# Power.net
KiCad netlist of a schematic drawn in Altium Designer
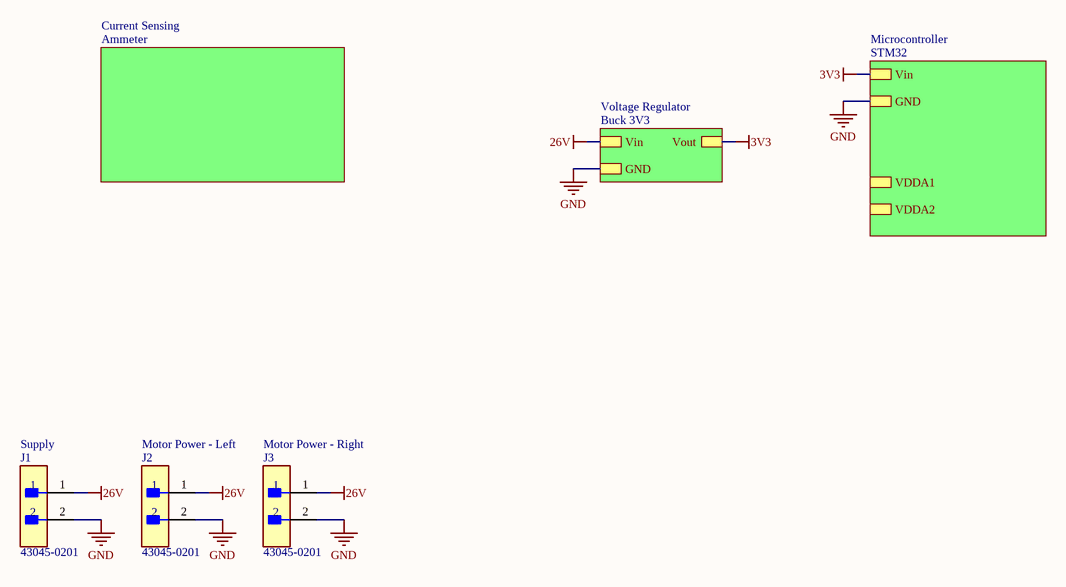
[diagram p0: Power.SchDoc]

(export (version "E")
  (design (tool "Eeschema 10.0.6"))
  (components
    (comp (ref "J1")
      (value "43045-0201")
      (footprint "FP-43045-0201-MFG")
      (description "CONN HEADER R/A 2POS")
      (libsource (lib "Altium Content Vault") (part "3bc925449376181038e59eaffc5286c"))
    )
    (comp (ref "J2")
      (value "43045-0201")
      (footprint "FP-43045-0201-MFG")
      (description "CONN HEADER R/A 2POS")
      (libsource (lib "Altium Content Vault") (part "3bc925449376181038e59eaffc5286c"))
    )
    (comp (ref "J3")
      (value "43045-0201")
      (footprint "FP-43045-0201-MFG")
      (description "CONN HEADER R/A 2POS")
      (libsource (lib "Altium Content Vault") (part "3bc925449376181038e59eaffc5286c"))
    )
  )
  (nets
    (net (code "4") (name "26V") (class "Default")
      (node (ref "J1") (pin "1") (pinfunction "1_1") (pintype "passive"))
      (node (ref "J2") (pin "1") (pinfunction "1_1") (pintype "passive"))
      (node (ref "J3") (pin "1") (pinfunction "1_1") (pintype "passive"))
    )
    (net (code "5") (name "GND") (class "Default")
      (node (ref "J1") (pin "2") (pinfunction "2_2") (pintype "passive"))
      (node (ref "J2") (pin "2") (pinfunction "2_2") (pintype "passive"))
      (node (ref "J3") (pin "2") (pinfunction "2_2") (pintype "passive"))
    )
  )
)
